# C_20.net
KiCad netlist of a schematic drawn in Altium Designer
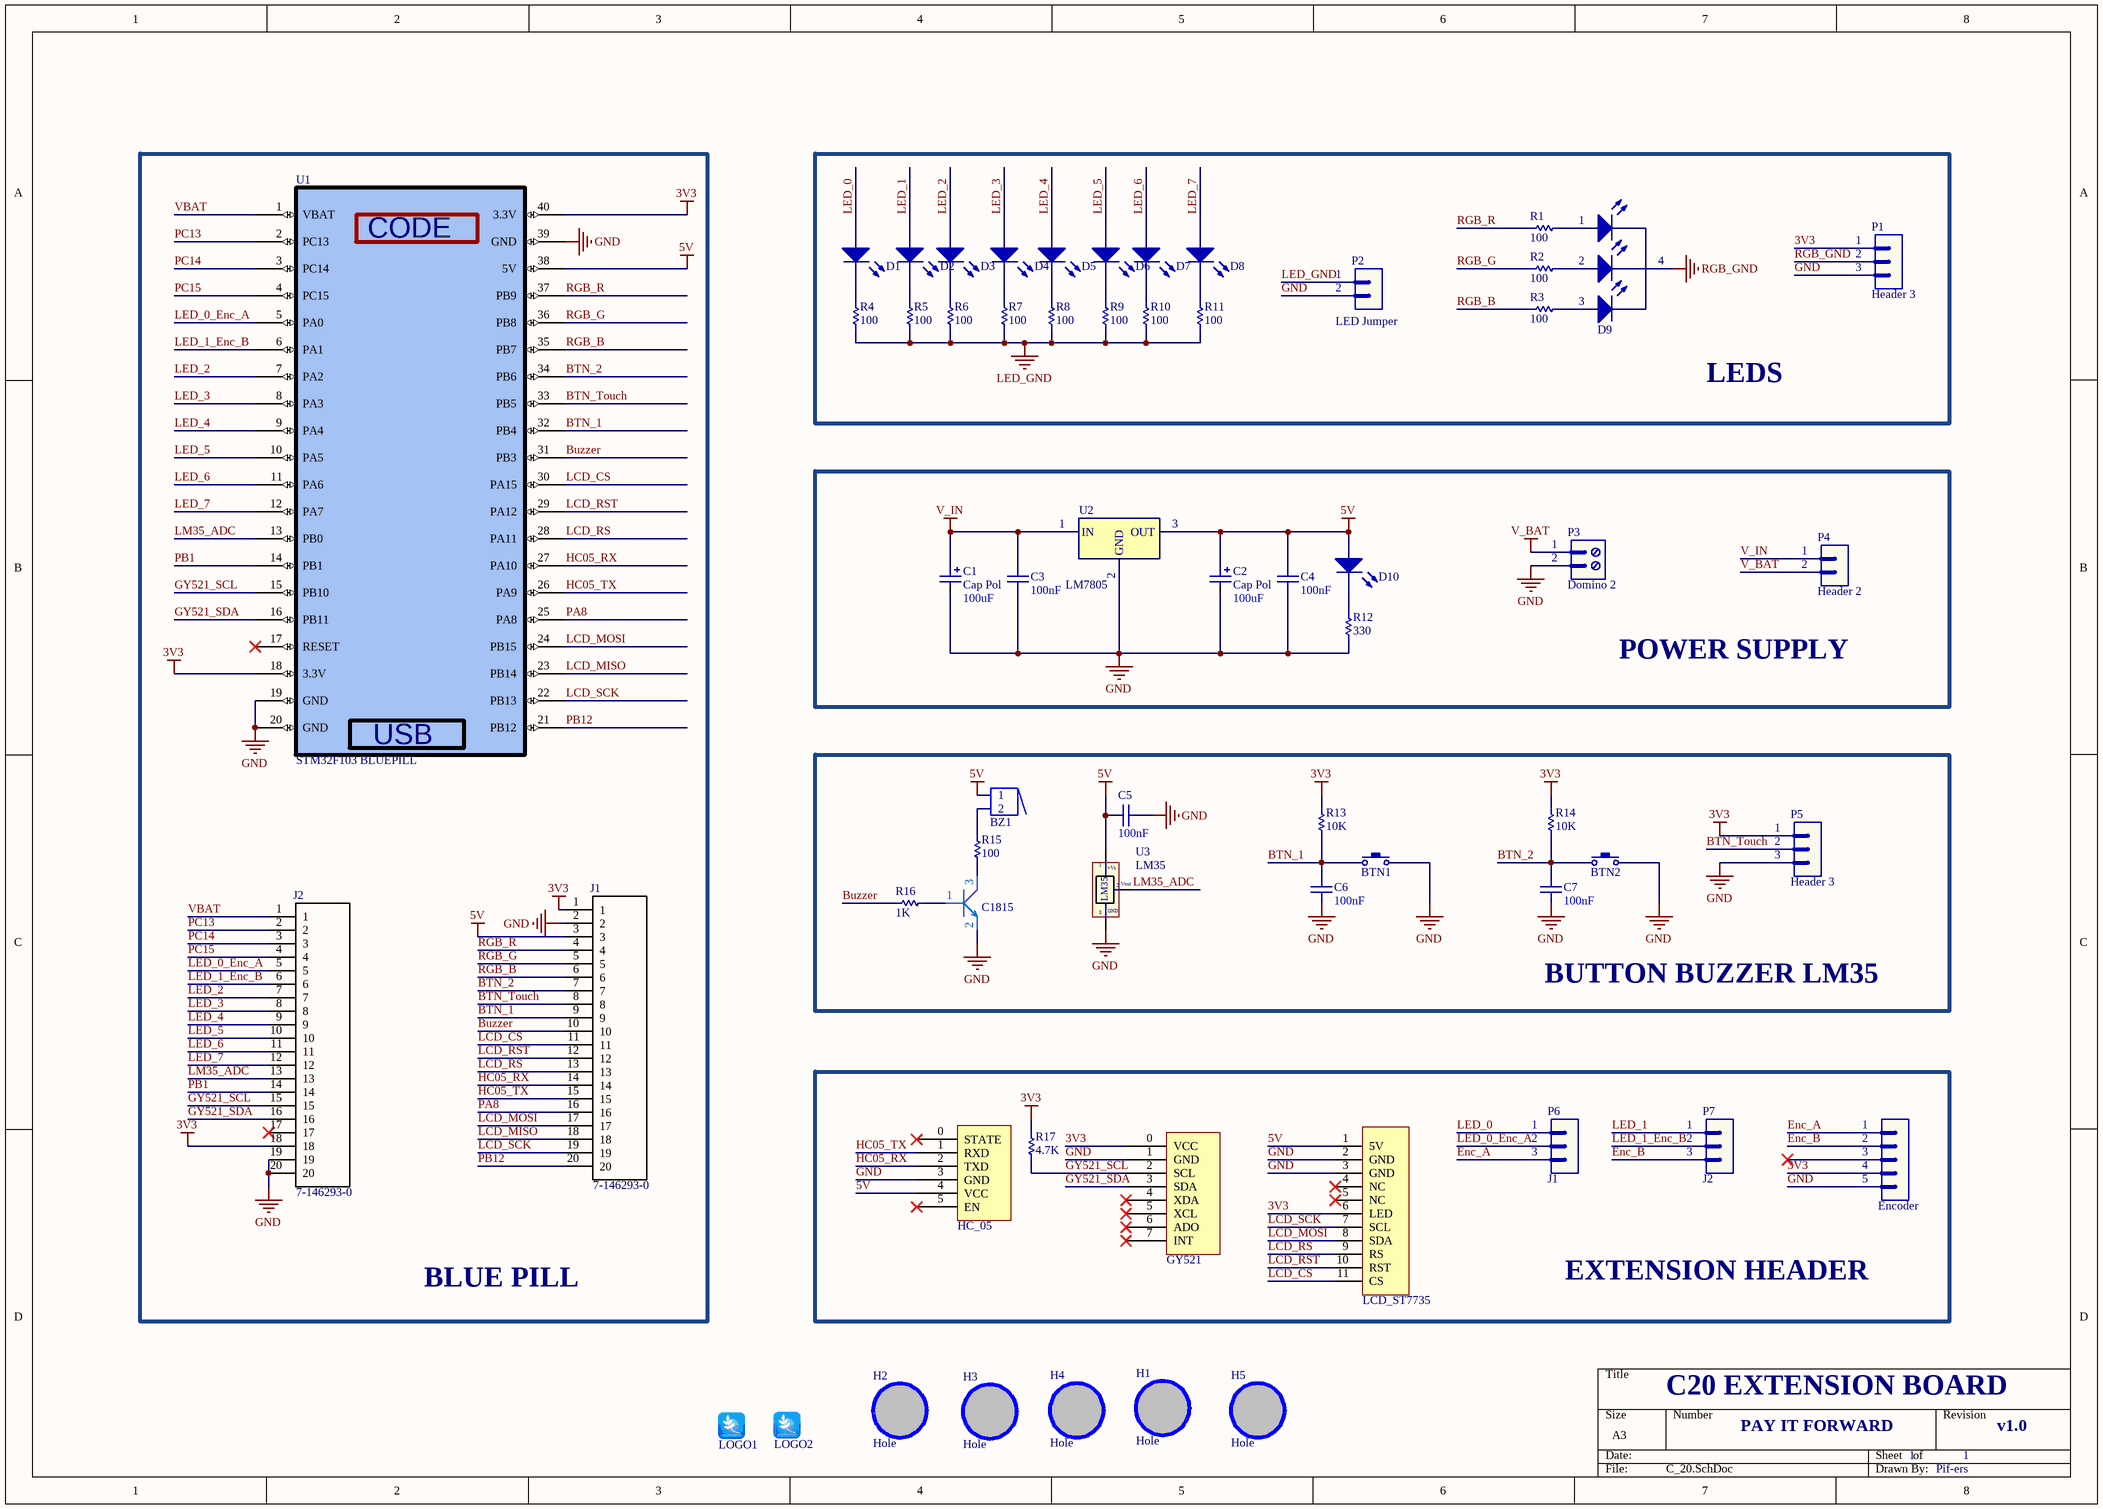
[diagram p0: C_20.SchDoc]

(export (version "E")
  (design (tool "Eeschema 10.0.6"))
  (components
    (comp (ref "BTN1")
      (value "Button")
      (footprint "Button")
      (libsource (lib "PIF_C16_2_lib") (part "Button"))
    )
    (comp (ref "BTN2")
      (value "Button")
      (footprint "Button")
      (libsource (lib "PIF_C16_2_lib") (part "Button"))
    )
    (comp (ref "BZ1") (value "Buzzer") (footprint "BUZZER") (libsource (lib "PIF_C16_2_lib") (part "Buzzer")))
    (comp (ref "C1")
      (value "Cap Pol")
      (footprint "CP1/2")
      (description "Polarized Capacitor (Radial)")
      (fields (field (name "ALTIUM_VALUE") "100uF"))
      (libsource (lib "PIF_C16_2_lib") (part "Cap Pol"))
    )
    (comp (ref "C2")
      (value "Cap Pol")
      (footprint "CP1/2")
      (description "Polarized Capacitor (Radial)")
      (fields (field (name "ALTIUM_VALUE") "100uF"))
      (libsource (lib "PIF_C16_2_lib") (part "Cap Pol"))
    )
    (comp (ref "C3")
      (value "100nF")
      (footprint "CAP-SM-0805")
      (description "Capacitor")
      (fields (field (name "Comment") "Cap Non-Pol SMD"))
      (libsource (lib "PIF_C16_2_lib") (part "Cap Non-Pol SMD"))
    )
    (comp (ref "C4")
      (value "100nF")
      (footprint "CAP-SM-0805")
      (description "Capacitor")
      (fields (field (name "Comment") "Cap Non-Pol SMD"))
      (libsource (lib "PIF_C16_2_lib") (part "Cap Non-Pol SMD"))
    )
    (comp (ref "C5")
      (value "100nF")
      (footprint "CAP-SM-0805")
      (description "Capacitor")
      (fields (field (name "Comment") "Cap Non-Pol SMD"))
      (libsource (lib "PIF_C16_2_lib") (part "Cap Non-Pol SMD"))
    )
    (comp (ref "C6")
      (value "100nF")
      (footprint "CAP-SM-0805")
      (description "Capacitor")
      (fields (field (name "Comment") "Cap Non-Pol SMD"))
      (libsource (lib "PIF_C16_2_lib") (part "Cap Non-Pol SMD"))
    )
    (comp (ref "C7")
      (value "100nF")
      (footprint "CAP-SM-0805")
      (description "Capacitor")
      (fields (field (name "Comment") "Cap Non-Pol SMD"))
      (libsource (lib "PIF_C16_2_lib") (part "Cap Non-Pol SMD"))
    )
    (comp (ref "C8") (value "C1815") (footprint "C1815_SMD") (libsource (lib "C_20_addition") (part "C1815")))
    (comp (ref "D1") (value "LED") (footprint "LED-3mm") (libsource (lib "PIF_C16_2_lib") (part "LED")))
    (comp (ref "D2") (value "LED") (footprint "LED-3mm") (libsource (lib "PIF_C16_2_lib") (part "LED")))
    (comp (ref "D3") (value "LED") (footprint "LED-3mm") (libsource (lib "PIF_C16_2_lib") (part "LED")))
    (comp (ref "D4") (value "LED") (footprint "LED-3mm") (libsource (lib "PIF_C16_2_lib") (part "LED")))
    (comp (ref "D5") (value "LED") (footprint "LED-3mm") (libsource (lib "PIF_C16_2_lib") (part "LED")))
    (comp (ref "D6") (value "LED") (footprint "LED-3mm") (libsource (lib "PIF_C16_2_lib") (part "LED")))
    (comp (ref "D7") (value "LED") (footprint "LED-3mm") (libsource (lib "PIF_C16_2_lib") (part "LED")))
    (comp (ref "D8") (value "LED") (footprint "LED-3mm") (libsource (lib "PIF_C16_2_lib") (part "LED")))
    (comp (ref "D9")
      (value "LED RGB")
      (footprint "LED RGB")
      (libsource (lib "PIF_C16_2_lib") (part "LED RGB"))
    )
    (comp (ref "D10") (value "LED") (footprint "LED-3mm") (libsource (lib "PIF_C16_2_lib") (part "LED")))
    (comp (ref "Encoder")
      (value "Encoder")
      (footprint "JP5")
      (description "Header, 5-Pin")
      (fields (field (name "PUBLISHER") "Altium Limited"))
      (libsource (lib "PIF_C16_2_lib") (part "Header 5"))
    )
    (comp (ref "H1")
      (value "Hole")
      (footprint "LO KHOAN 3MM")
      (description "Hole 3mm")
      (libsource (lib "PIF_C16_2_lib") (part "Hole"))
    )
    (comp (ref "H2")
      (value "Hole")
      (footprint "LO KHOAN 3MM")
      (description "Hole 3mm")
      (libsource (lib "PIF_C16_2_lib") (part "Hole"))
    )
    (comp (ref "H3")
      (value "Hole")
      (footprint "LO KHOAN 3MM")
      (description "Hole 3mm")
      (libsource (lib "PIF_C16_2_lib") (part "Hole"))
    )
    (comp (ref "H4")
      (value "Hole")
      (footprint "LO KHOAN 3MM")
      (description "Hole 3mm")
      (libsource (lib "PIF_C16_2_lib") (part "Hole"))
    )
    (comp (ref "H5")
      (value "Hole")
      (footprint "LO KHOAN 3MM")
      (description "Hole 3mm")
      (libsource (lib "PIF_C16_2_lib") (part "Hole"))
    )
    (comp (ref "HC_05") (value "HC_05") (footprint "HC_05") (libsource (lib "C_20_addition") (part "HC_05")))
    (comp (ref "J1")
      (value "7-146293-0")
      (footprint "*TE_7-146293-0")
      (libsource (lib "7-146293-0") (part "7-146293-0"))
    )
    (comp (ref "J2")
      (value "7-146293-0")
      (footprint "*TE_7-146293-0")
      (libsource (lib "7-146293-0") (part "7-146293-0"))
    )
    (comp (ref "LCD_ST7735")
      (value "LCD_ST7735")
      (footprint "LCD_ST7735")
      (libsource (lib "C_20_addition") (part "LCD_ST7735"))
    )
    (comp (ref "LOGO1")
      (value "LOGO PIF")
      (footprint "PIF LOGO TOP OVERLAY")
      (libsource (lib "logo_PIF") (part "LOGO PIF"))
    )
    (comp (ref "LOGO2")
      (value "LOGO PIF")
      (footprint "PIF LOGO BOTTOM LAYER")
      (libsource (lib "logo_PIF") (part "LOGO PIF"))
    )
    (comp (ref "MPU6050")
      (value "GY521")
      (footprint "GY521_MPU6050")
      (libsource (lib "C_20_addition") (part "GY521_MPU6050"))
    )
    (comp (ref "P1")
      (value "Header 3")
      (footprint "JP3")
      (description "Header, 3-Pin")
      (fields (field (name "PUBLISHER") "Altium Limited"))
      (libsource (lib "PIF_C16_2_lib") (part "Header 3"))
    )
    (comp (ref "P2")
      (value "LED Jumper")
      (footprint "JP2")
      (description "Header, 2-Pin")
      (fields (field (name "PUBLISHER") "Altium Limited"))
      (libsource (lib "PIF_C16_2_lib") (part "Header 2"))
    )
    (comp (ref "P3")
      (value "Domino 2")
      (footprint "DOMINO 2- 5mm")
      (description "Domino, 2-Pin")
      (fields (field (name "PUBLISHER") "Altium Limited"))
      (libsource (lib "PIF_C16_2_lib") (part "Domino 2"))
    )
    (comp (ref "P4")
      (value "Header 2")
      (footprint "JP2")
      (description "Header, 2-Pin")
      (fields (field (name "PUBLISHER") "Altium Limited"))
      (libsource (lib "PIF_C16_2_lib") (part "Header 2"))
    )
    (comp (ref "P5")
      (value "Header 3")
      (footprint "JP3")
      (description "Header, 3-Pin")
      (fields (field (name "PUBLISHER") "Altium Limited"))
      (libsource (lib "PIF_C16_2_lib") (part "Header 3"))
    )
    (comp (ref "P6")
      (value "J1")
      (footprint "JP3")
      (description "Header, 3-Pin")
      (fields (field (name "PUBLISHER") "Altium Limited"))
      (libsource (lib "PIF_C16_2_lib") (part "Header 3"))
    )
    (comp (ref "P7")
      (value "J2")
      (footprint "JP3")
      (description "Header, 3-Pin")
      (fields (field (name "PUBLISHER") "Altium Limited"))
      (libsource (lib "PIF_C16_2_lib") (part "Header 3"))
    )
    (comp (ref "R1")
      (value "100")
      (footprint "RES-SM-0805")
      (fields (field (name "Comment") "Resistor 1/4W"))
      (libsource (lib "PIF_C16_2_lib") (part "RES"))
    )
    (comp (ref "R2")
      (value "100")
      (footprint "RES-SM-0805")
      (fields (field (name "Comment") "Resistor 1/4W"))
      (libsource (lib "PIF_C16_2_lib") (part "RES"))
    )
    (comp (ref "R3")
      (value "100")
      (footprint "RES-SM-0805")
      (fields (field (name "Comment") "Resistor 1/4W"))
      (libsource (lib "PIF_C16_2_lib") (part "RES"))
    )
    (comp (ref "R4")
      (value "100")
      (footprint "RES-SM-0805")
      (fields (field (name "Comment") "Resistor 1/4W"))
      (libsource (lib "PIF_C16_2_lib") (part "RES"))
    )
    (comp (ref "R5")
      (value "100")
      (footprint "RES-SM-0805")
      (fields (field (name "Comment") "Resistor 1/4W"))
      (libsource (lib "PIF_C16_2_lib") (part "RES"))
    )
    (comp (ref "R6")
      (value "100")
      (footprint "RES-SM-0805")
      (fields (field (name "Comment") "Resistor 1/4W"))
      (libsource (lib "PIF_C16_2_lib") (part "RES"))
    )
    (comp (ref "R7")
      (value "100")
      (footprint "RES-SM-0805")
      (fields (field (name "Comment") "Resistor 1/4W"))
      (libsource (lib "PIF_C16_2_lib") (part "RES"))
    )
    (comp (ref "R8")
      (value "100")
      (footprint "RES-SM-0805")
      (fields (field (name "Comment") "Resistor 1/4W"))
      (libsource (lib "PIF_C16_2_lib") (part "RES"))
    )
    (comp (ref "R9")
      (value "100")
      (footprint "RES-SM-0805")
      (fields (field (name "Comment") "Resistor 1/4W"))
      (libsource (lib "PIF_C16_2_lib") (part "RES"))
    )
    (comp (ref "R10")
      (value "100")
      (footprint "RES-SM-0805")
      (fields (field (name "Comment") "Resistor 1/4W"))
      (libsource (lib "PIF_C16_2_lib") (part "RES"))
    )
    (comp (ref "R11")
      (value "100")
      (footprint "RES-SM-0805")
      (fields (field (name "Comment") "Resistor 1/4W"))
      (libsource (lib "PIF_C16_2_lib") (part "RES"))
    )
    (comp (ref "R12")
      (value "330")
      (footprint "RES-SM-0805")
      (fields (field (name "Comment") "Resistor 1/4W"))
      (libsource (lib "PIF_C16_2_lib") (part "RES"))
    )
    (comp (ref "R13")
      (value "10K")
      (footprint "RES-SM-0805")
      (fields (field (name "Comment") "Resistor 1/4W"))
      (libsource (lib "PIF_C16_2_lib") (part "RES"))
    )
    (comp (ref "R14")
      (value "10K")
      (footprint "RES-SM-0805")
      (fields (field (name "Comment") "Resistor 1/4W"))
      (libsource (lib "PIF_C16_2_lib") (part "RES"))
    )
    (comp (ref "R15")
      (value "100")
      (footprint "RES-SM-0805")
      (fields (field (name "Comment") "Resistor 1/4W"))
      (libsource (lib "PIF_C16_2_lib") (part "RES"))
    )
    (comp (ref "R16")
      (value "1K")
      (footprint "RES-SM-0805")
      (fields (field (name "Comment") "Resistor 1/4W"))
      (libsource (lib "PIF_C16_2_lib") (part "RES"))
    )
    (comp (ref "R17")
      (value "4.7K")
      (footprint "RES-SM-0805")
      (fields (field (name "Comment") "Resistor 1/4W"))
      (libsource (lib "PIF_C16_2_lib") (part "RES"))
    )
    (comp (ref "U1")
      (value "STM32F103 BLUEPILL")
      (footprint "STM32F103 Bluepill")
      (libsource (lib "BluePillLib") (part "STM32F103 BLUEPILL"))
    )
    (comp (ref "U2")
      (value "LM7805")
      (footprint "QTO-220")
      (description "Positive Voltage Regulator")
      (libsource (lib "PIF_C16_2_lib") (part "LM7805"))
    )
    (comp (ref "U3")
      (value "LM35")
      (footprint "QTO-92")
      (description "Teminal")
      (libsource (lib "syhaunguyen") (part "LM35"))
    )
  )
  (nets
    (net (code "1") (name "/BTN_1") (class "Default")
      (node (ref "BTN1") (pin "1") (pintype "passive"))
      (node (ref "C6") (pin "2") (pinfunction "2_2") (pintype "passive"))
      (node (ref "J1") (pin "9") (pinfunction "9_9") (pintype "passive"))
      (node (ref "R13") (pin "1") (pintype "passive"))
      (node (ref "U1") (pin "32") (pinfunction "PB4_32") (pintype "bidirectional"))
    )
    (net (code "2") (name "/BTN_2") (class "Default")
      (node (ref "BTN2") (pin "1") (pintype "passive"))
      (node (ref "C7") (pin "2") (pinfunction "2_2") (pintype "passive"))
      (node (ref "J1") (pin "7") (pinfunction "7_7") (pintype "passive"))
      (node (ref "R14") (pin "1") (pintype "passive"))
      (node (ref "U1") (pin "34") (pinfunction "PB6_34") (pintype "bidirectional"))
    )
    (net (code "3") (name "/BTN_Touch") (class "Default")
      (node (ref "J1") (pin "8") (pinfunction "8_8") (pintype "passive"))
      (node (ref "P5") (pin "2") (pinfunction "2_2") (pintype "passive"))
      (node (ref "U1") (pin "33") (pinfunction "PB5_33") (pintype "bidirectional"))
    )
    (net (code "4") (name "/Buzzer") (class "Default")
      (node (ref "J1") (pin "10") (pinfunction "10_10") (pintype "passive"))
      (node (ref "R16") (pin "1") (pintype "passive"))
      (node (ref "U1") (pin "31") (pinfunction "PB3_31") (pintype "bidirectional"))
    )
    (net (code "5") (name "/Enc_A") (class "Default")
      (node (ref "Encoder") (pin "1") (pinfunction "1_1") (pintype "passive"))
      (node (ref "P6") (pin "3") (pinfunction "3_3") (pintype "passive"))
    )
    (net (code "6") (name "/Enc_B") (class "Default")
      (node (ref "Encoder") (pin "2") (pinfunction "2_2") (pintype "passive"))
      (node (ref "P7") (pin "3") (pinfunction "3_3") (pintype "passive"))
    )
    (net (code "7") (name "/GY521_SCL") (class "Default")
      (node (ref "J2") (pin "15") (pinfunction "15_15") (pintype "passive"))
      (node (ref "MPU6050") (pin "2") (pinfunction "SCL_2") (pintype "passive"))
      (node (ref "R17") (pin "1") (pintype "passive"))
      (node (ref "U1") (pin "15") (pinfunction "PB10_15") (pintype "bidirectional"))
    )
    (net (code "8") (name "/GY521_SDA") (class "Default")
      (node (ref "J2") (pin "16") (pinfunction "16_16") (pintype "passive"))
      (node (ref "MPU6050") (pin "3") (pinfunction "SDA_3") (pintype "passive"))
      (node (ref "U1") (pin "16") (pinfunction "PB11_16") (pintype "bidirectional"))
    )
    (net (code "9") (name "/HC05_RX") (class "Default")
      (node (ref "HC_05") (pin "2") (pinfunction "TXD_2") (pintype "passive"))
      (node (ref "J1") (pin "14") (pinfunction "14_14") (pintype "passive"))
      (node (ref "U1") (pin "27") (pinfunction "PA10_27") (pintype "bidirectional"))
    )
    (net (code "10") (name "/HC05_TX") (class "Default")
      (node (ref "HC_05") (pin "1") (pinfunction "RXD_1") (pintype "passive"))
      (node (ref "J1") (pin "15") (pinfunction "15_15") (pintype "passive"))
      (node (ref "U1") (pin "26") (pinfunction "PA9_26") (pintype "bidirectional"))
    )
    (net (code "11") (name "/LCD_CS") (class "Default")
      (node (ref "J1") (pin "11") (pinfunction "11_11") (pintype "passive"))
      (node (ref "LCD_ST7735") (pin "11") (pinfunction "CS_11") (pintype "passive"))
      (node (ref "U1") (pin "30") (pinfunction "PA15_30") (pintype "bidirectional"))
    )
    (net (code "12") (name "/LCD_MISO") (class "Default")
      (node (ref "J1") (pin "18") (pinfunction "18_18") (pintype "passive"))
      (node (ref "U1") (pin "23") (pinfunction "PB14_23") (pintype "bidirectional"))
    )
    (net (code "13") (name "/LCD_MOSI") (class "Default")
      (node (ref "J1") (pin "17") (pinfunction "17_17") (pintype "passive"))
      (node (ref "LCD_ST7735") (pin "8") (pinfunction "SDA_8") (pintype "passive"))
      (node (ref "U1") (pin "24") (pinfunction "PB15_24") (pintype "bidirectional"))
    )
    (net (code "14") (name "/LCD_RS") (class "Default")
      (node (ref "J1") (pin "13") (pinfunction "13_13") (pintype "passive"))
      (node (ref "LCD_ST7735") (pin "9") (pinfunction "RS_9") (pintype "passive"))
      (node (ref "U1") (pin "28") (pinfunction "PA11_28") (pintype "bidirectional"))
    )
    (net (code "15") (name "/LCD_RST") (class "Default")
      (node (ref "J1") (pin "12") (pinfunction "12_12") (pintype "passive"))
      (node (ref "LCD_ST7735") (pin "10") (pinfunction "RST_10") (pintype "passive"))
      (node (ref "U1") (pin "29") (pinfunction "PA12_29") (pintype "bidirectional"))
    )
    (net (code "16") (name "/LCD_SCK") (class "Default")
      (node (ref "J1") (pin "19") (pinfunction "19_19") (pintype "passive"))
      (node (ref "LCD_ST7735") (pin "7") (pinfunction "SCL_7") (pintype "passive"))
      (node (ref "U1") (pin "22") (pinfunction "PB13_22") (pintype "bidirectional"))
    )
    (net (code "17") (name "/LED_0") (class "Default")
      (node (ref "D1") (pin "1") (pinfunction "A_1") (pintype "passive"))
      (node (ref "P6") (pin "1") (pinfunction "1_1") (pintype "passive"))
    )
    (net (code "18") (name "/LED_0_Enc_A") (class "Default")
      (node (ref "J2") (pin "5") (pinfunction "5_5") (pintype "passive"))
      (node (ref "P6") (pin "2") (pinfunction "2_2") (pintype "passive"))
      (node (ref "U1") (pin "5") (pinfunction "PA0_5") (pintype "bidirectional"))
    )
    (net (code "19") (name "/LED_1") (class "Default")
      (node (ref "D2") (pin "1") (pinfunction "A_1") (pintype "passive"))
      (node (ref "P7") (pin "1") (pinfunction "1_1") (pintype "passive"))
    )
    (net (code "20") (name "/LED_1_Enc_B") (class "Default")
      (node (ref "J2") (pin "6") (pinfunction "6_6") (pintype "passive"))
      (node (ref "P7") (pin "2") (pinfunction "2_2") (pintype "passive"))
      (node (ref "U1") (pin "6") (pinfunction "PA1_6") (pintype "bidirectional"))
    )
    (net (code "21") (name "/LED_2") (class "Default")
      (node (ref "D3") (pin "1") (pinfunction "A_1") (pintype "passive"))
      (node (ref "J2") (pin "7") (pinfunction "7_7") (pintype "passive"))
      (node (ref "U1") (pin "7") (pinfunction "PA2_7") (pintype "bidirectional"))
    )
    (net (code "22") (name "/LED_3") (class "Default")
      (node (ref "D4") (pin "1") (pinfunction "A_1") (pintype "passive"))
      (node (ref "J2") (pin "8") (pinfunction "8_8") (pintype "passive"))
      (node (ref "U1") (pin "8") (pinfunction "PA3_8") (pintype "bidirectional"))
    )
    (net (code "23") (name "/LED_4") (class "Default")
      (node (ref "D5") (pin "1") (pinfunction "A_1") (pintype "passive"))
      (node (ref "J2") (pin "9") (pinfunction "9_9") (pintype "passive"))
      (node (ref "U1") (pin "9") (pinfunction "PA4_9") (pintype "bidirectional"))
    )
    (net (code "24") (name "/LED_5") (class "Default")
      (node (ref "D6") (pin "1") (pinfunction "A_1") (pintype "passive"))
      (node (ref "J2") (pin "10") (pinfunction "10_10") (pintype "passive"))
      (node (ref "U1") (pin "10") (pinfunction "PA5_10") (pintype "bidirectional"))
    )
    (net (code "25") (name "/LED_6") (class "Default")
      (node (ref "D7") (pin "1") (pinfunction "A_1") (pintype "passive"))
      (node (ref "J2") (pin "11") (pinfunction "11_11") (pintype "passive"))
      (node (ref "U1") (pin "11") (pinfunction "PA6_11") (pintype "bidirectional"))
    )
    (net (code "26") (name "/LED_7") (class "Default")
      (node (ref "D8") (pin "1") (pinfunction "A_1") (pintype "passive"))
      (node (ref "J2") (pin "12") (pinfunction "12_12") (pintype "passive"))
      (node (ref "U1") (pin "12") (pinfunction "PA7_12") (pintype "bidirectional"))
    )
    (net (code "27") (name "/LM35_ADC") (class "Default")
      (node (ref "J2") (pin "13") (pinfunction "13_13") (pintype "passive"))
      (node (ref "U1") (pin "13") (pinfunction "PB0_13") (pintype "bidirectional"))
      (node (ref "U3") (pin "2") (pinfunction "Vout_2") (pintype "passive"))
    )
    (net (code "28") (name "/PA8") (class "Default")
      (node (ref "J1") (pin "16") (pinfunction "16_16") (pintype "passive"))
      (node (ref "U1") (pin "25") (pinfunction "PA8_25") (pintype "bidirectional"))
    )
    (net (code "29") (name "/PB1") (class "Default")
      (node (ref "J2") (pin "14") (pinfunction "14_14") (pintype "passive"))
      (node (ref "U1") (pin "14") (pinfunction "PB1_14") (pintype "bidirectional"))
    )
    (net (code "30") (name "/PB12") (class "Default")
      (node (ref "J1") (pin "20") (pinfunction "20_20") (pintype "passive"))
      (node (ref "U1") (pin "21") (pinfunction "PB12_21") (pintype "bidirectional"))
    )
    (net (code "31") (name "/PC13") (class "Default")
      (node (ref "J2") (pin "2") (pinfunction "2_2") (pintype "passive"))
      (node (ref "U1") (pin "2") (pinfunction "PC13_2") (pintype "bidirectional"))
    )
    (net (code "32") (name "/PC14") (class "Default")
      (node (ref "J2") (pin "3") (pinfunction "3_3") (pintype "passive"))
      (node (ref "U1") (pin "3") (pinfunction "PC14_3") (pintype "bidirectional"))
    )
    (net (code "33") (name "/PC15") (class "Default")
      (node (ref "J2") (pin "4") (pinfunction "4_4") (pintype "passive"))
      (node (ref "U1") (pin "4") (pinfunction "PC15_4") (pintype "bidirectional"))
    )
    (net (code "34") (name "/RGB_B") (class "Default")
      (node (ref "J1") (pin "6") (pinfunction "6_6") (pintype "passive"))
      (node (ref "R3") (pin "1") (pintype "passive"))
      (node (ref "U1") (pin "35") (pinfunction "PB7_35") (pintype "bidirectional"))
    )
    (net (code "35") (name "/RGB_G") (class "Default")
      (node (ref "J1") (pin "5") (pinfunction "5_5") (pintype "passive"))
      (node (ref "R2") (pin "1") (pintype "passive"))
      (node (ref "U1") (pin "36") (pinfunction "PB8_36") (pintype "bidirectional"))
    )
    (net (code "36") (name "/RGB_R") (class "Default")
      (node (ref "J1") (pin "4") (pinfunction "4_4") (pintype "passive"))
      (node (ref "R1") (pin "1") (pintype "passive"))
      (node (ref "U1") (pin "37") (pinfunction "PB9_37") (pintype "bidirectional"))
    )
    (net (code "37") (name "/VBAT") (class "Default")
      (node (ref "J2") (pin "1") (pinfunction "1_1") (pintype "passive"))
      (node (ref "U1") (pin "1") (pinfunction "VBAT_1") (pintype "bidirectional"))
    )
    (net (code "38") (name "3V3") (class "Default")
      (node (ref "Encoder") (pin "4") (pinfunction "4_4") (pintype "passive"))
      (node (ref "J1") (pin "1") (pinfunction "1_1") (pintype "passive"))
      (node (ref "J2") (pin "18") (pinfunction "18_18") (pintype "passive"))
      (node (ref "LCD_ST7735") (pin "6") (pinfunction "LED_6") (pintype "passive"))
      (node (ref "MPU6050") (pin "0") (pinfunction "VCC_0") (pintype "passive"))
      (node (ref "P1") (pin "1") (pinfunction "1_1") (pintype "passive"))
      (node (ref "P5") (pin "1") (pinfunction "1_1") (pintype "passive"))
      (node (ref "R13") (pin "2") (pintype "passive"))
      (node (ref "R14") (pin "2") (pintype "passive"))
      (node (ref "R17") (pin "2") (pintype "passive"))
      (node (ref "U1") (pin "18") (pinfunction "3.3V_18") (pintype "bidirectional"))
      (node (ref "U1") (pin "40") (pinfunction "3.3V_40") (pintype "bidirectional"))
    )
    (net (code "39") (name "5V") (class "Default")
      (node (ref "BZ1") (pin "1") (pinfunction "1_1") (pintype "passive"))
      (node (ref "C2") (pin "1") (pinfunction "1_1") (pintype "passive"))
      (node (ref "C4") (pin "2") (pinfunction "2_2") (pintype "passive"))
      (node (ref "C5") (pin "1") (pinfunction "1_1") (pintype "passive"))
      (node (ref "D10") (pin "1") (pinfunction "A_1") (pintype "passive"))
      (node (ref "HC_05") (pin "4") (pinfunction "VCC_4") (pintype "passive"))
      (node (ref "J1") (pin "3") (pinfunction "3_3") (pintype "passive"))
      (node (ref "LCD_ST7735") (pin "1") (pinfunction "5V_1") (pintype "passive"))
      (node (ref "U1") (pin "38") (pinfunction "5V_38") (pintype "bidirectional"))
      (node (ref "U2") (pin "3") (pinfunction "OUT_3") (pintype "power_in"))
      (node (ref "U3") (pin "1") (pinfunction "+Vs_1") (pintype "passive"))
    )
    (net (code "40") (name "GND") (class "Default")
      (node (ref "BTN1") (pin "2") (pintype "passive"))
      (node (ref "BTN2") (pin "2") (pintype "passive"))
      (node (ref "C1") (pin "2") (pinfunction "2_2") (pintype "passive"))
      (node (ref "C2") (pin "2") (pinfunction "2_2") (pintype "passive"))
      (node (ref "C3") (pin "1") (pinfunction "1_1") (pintype "passive"))
      (node (ref "C4") (pin "1") (pinfunction "1_1") (pintype "passive"))
      (node (ref "C5") (pin "2") (pinfunction "2_2") (pintype "passive"))
      (node (ref "C6") (pin "1") (pinfunction "1_1") (pintype "passive"))
      (node (ref "C7") (pin "1") (pinfunction "1_1") (pintype "passive"))
      (node (ref "C8") (pin "2") (pinfunction "C_2") (pintype "passive"))
      (node (ref "Encoder") (pin "5") (pinfunction "5_5") (pintype "passive"))
      (node (ref "HC_05") (pin "3") (pinfunction "GND_3") (pintype "passive"))
      (node (ref "J1") (pin "2") (pinfunction "2_2") (pintype "passive"))
      (node (ref "J2") (pin "19") (pinfunction "19_19") (pintype "passive"))
      (node (ref "J2") (pin "20") (pinfunction "20_20") (pintype "passive"))
      (node (ref "LCD_ST7735") (pin "2") (pinfunction "GND_2") (pintype "passive"))
      (node (ref "LCD_ST7735") (pin "3") (pinfunction "GND_3") (pintype "passive"))
      (node (ref "MPU6050") (pin "1") (pinfunction "GND_1") (pintype "passive"))
      (node (ref "P1") (pin "3") (pinfunction "3_3") (pintype "passive"))
      (node (ref "P2") (pin "2") (pinfunction "2_2") (pintype "passive"))
      (node (ref "P3") (pin "2") (pinfunction "2_2") (pintype "passive"))
      (node (ref "P5") (pin "3") (pinfunction "3_3") (pintype "passive"))
      (node (ref "R12") (pin "1") (pintype "passive"))
      (node (ref "U1") (pin "19") (pinfunction "GND_19") (pintype "bidirectional"))
      (node (ref "U1") (pin "20") (pinfunction "GND_20") (pintype "bidirectional"))
      (node (ref "U1") (pin "39") (pinfunction "GND_39") (pintype "bidirectional"))
      (node (ref "U2") (pin "2") (pinfunction "GND_2") (pintype "power_in"))
      (node (ref "U3") (pin "3") (pinfunction "-_3") (pintype "passive"))
    )
    (net (code "41") (name "LED_GND") (class "Default")
      (node (ref "P2") (pin "1") (pinfunction "1_1") (pintype "passive"))
      (node (ref "R10") (pin "1") (pintype "passive"))
      (node (ref "R11") (pin "1") (pintype "passive"))
      (node (ref "R4") (pin "1") (pintype "passive"))
      (node (ref "R5") (pin "1") (pintype "passive"))
      (node (ref "R6") (pin "1") (pintype "passive"))
      (node (ref "R7") (pin "1") (pintype "passive"))
      (node (ref "R8") (pin "1") (pintype "passive"))
      (node (ref "R9") (pin "1") (pintype "passive"))
    )
    (net (code "42") (name "Net-(BZ1-Pad2)") (class "Default")
      (node (ref "BZ1") (pin "2") (pinfunction "2_2") (pintype "passive"))
      (node (ref "R15") (pin "2") (pintype "passive"))
    )
    (net (code "43") (name "Net-(C8-B)") (class "Default")
      (node (ref "C8") (pin "1") (pinfunction "B_1") (pintype "passive"))
      (node (ref "R16") (pin "2") (pintype "passive"))
    )
    (net (code "44") (name "Net-(C8-C-Pad3)") (class "Default")
      (node (ref "C8") (pin "3") (pinfunction "C_3") (pintype "passive"))
      (node (ref "R15") (pin "1") (pintype "passive"))
    )
    (net (code "45") (name "Net-(D1-K)") (class "Default")
      (node (ref "D1") (pin "2") (pinfunction "K_2") (pintype "passive"))
      (node (ref "R4") (pin "2") (pintype "passive"))
    )
    (net (code "46") (name "Net-(D2-K)") (class "Default")
      (node (ref "D2") (pin "2") (pinfunction "K_2") (pintype "passive"))
      (node (ref "R5") (pin "2") (pintype "passive"))
    )
    (net (code "47") (name "Net-(D3-K)") (class "Default")
      (node (ref "D3") (pin "2") (pinfunction "K_2") (pintype "passive"))
      (node (ref "R6") (pin "2") (pintype "passive"))
    )
    (net (code "48") (name "Net-(D4-K)") (class "Default")
      (node (ref "D4") (pin "2") (pinfunction "K_2") (pintype "passive"))
      (node (ref "R7") (pin "2") (pintype "passive"))
    )
    (net (code "49") (name "Net-(D5-K)") (class "Default")
      (node (ref "D5") (pin "2") (pinfunction "K_2") (pintype "passive"))
      (node (ref "R8") (pin "2") (pintype "passive"))
    )
    (net (code "50") (name "Net-(D6-K)") (class "Default")
      (node (ref "D6") (pin "2") (pinfunction "K_2") (pintype "passive"))
      (node (ref "R9") (pin "2") (pintype "passive"))
    )
    (net (code "51") (name "Net-(D7-K)") (class "Default")
      (node (ref "D7") (pin "2") (pinfunction "K_2") (pintype "passive"))
      (node (ref "R10") (pin "2") (pintype "passive"))
    )
    (net (code "52") (name "Net-(D8-K)") (class "Default")
      (node (ref "D8") (pin "2") (pinfunction "K_2") (pintype "passive"))
      (node (ref "R11") (pin "2") (pintype "passive"))
    )
    (net (code "53") (name "Net-(D9-Anod-Pad1)") (class "Default")
      (node (ref "D9") (pin "1") (pinfunction "Anod_1") (pintype "passive"))
      (node (ref "R1") (pin "2") (pintype "passive"))
    )
    (net (code "54") (name "Net-(D9-Anod-Pad2)") (class "Default")
      (node (ref "D9") (pin "2") (pinfunction "Anod_2") (pintype "passive"))
      (node (ref "R2") (pin "2") (pintype "passive"))
    )
    (net (code "55") (name "Net-(D9-Anod-Pad3)") (class "Default")
      (node (ref "D9") (pin "3") (pinfunction "Anod_3") (pintype "passive"))
      (node (ref "R3") (pin "2") (pintype "passive"))
    )
    (net (code "56") (name "Net-(D10-K)") (class "Default")
      (node (ref "D10") (pin "2") (pinfunction "K_2") (pintype "passive"))
      (node (ref "R12") (pin "2") (pintype "passive"))
    )
    (net (code "57") (name "RGB_GND") (class "Default")
      (node (ref "D9") (pin "4") (pinfunction "Anod_4") (pintype "passive"))
      (node (ref "P1") (pin "2") (pinfunction "2_2") (pintype "passive"))
    )
    (net (code "58") (name "V_BAT") (class "Default")
      (node (ref "P3") (pin "1") (pinfunction "1_1") (pintype "passive"))
      (node (ref "P4") (pin "2") (pinfunction "2_2") (pintype "passive"))
    )
    (net (code "59") (name "V_IN") (class "Default")
      (node (ref "C1") (pin "1") (pinfunction "1_1") (pintype "passive"))
      (node (ref "C3") (pin "2") (pinfunction "2_2") (pintype "passive"))
      (node (ref "P4") (pin "1") (pinfunction "1_1") (pintype "passive"))
      (node (ref "U2") (pin "1") (pinfunction "IN_1") (pintype "power_in"))
    )
    (net (code "60") (name "unconnected-(Encoder-Pad3)") (class "Default")
      (node (ref "Encoder") (pin "3") (pinfunction "3_3") (pintype "passive+no_connect"))
    )
    (net (code "61") (name "unconnected-(H1-Pad1)") (class "Default")
      (node (ref "H1") (pin "1") (pinfunction "1_1") (pintype "passive"))
    )
    (net (code "62") (name "unconnected-(H2-Pad1)") (class "Default")
      (node (ref "H2") (pin "1") (pinfunction "1_1") (pintype "passive"))
    )
    (net (code "63") (name "unconnected-(H3-Pad1)") (class "Default")
      (node (ref "H3") (pin "1") (pinfunction "1_1") (pintype "passive"))
    )
    (net (code "64") (name "unconnected-(H4-Pad1)") (class "Default")
      (node (ref "H4") (pin "1") (pinfunction "1_1") (pintype "passive"))
    )
    (net (code "65") (name "unconnected-(H5-Pad1)") (class "Default")
      (node (ref "H5") (pin "1") (pinfunction "1_1") (pintype "passive"))
    )
    (net (code "66") (name "unconnected-(HC_05-EN-Pad5)") (class "Default")
      (node (ref "HC_05") (pin "5") (pinfunction "EN_5") (pintype "passive+no_connect"))
    )
    (net (code "67") (name "unconnected-(HC_05-STATE-Pad0)") (class "Default")
      (node (ref "HC_05") (pin "0") (pinfunction "STATE_0") (pintype "passive+no_connect"))
    )
    (net (code "68") (name "unconnected-(J2-Pad17)") (class "Default")
      (node (ref "J2") (pin "17") (pinfunction "17_17") (pintype "passive+no_connect"))
    )
    (net (code "69") (name "unconnected-(LCD_ST7735-NC-Pad4)") (class "Default")
      (node (ref "LCD_ST7735") (pin "4") (pinfunction "NC_4") (pintype "passive+no_connect"))
    )
    (net (code "70") (name "unconnected-(LCD_ST7735-NC-Pad5)") (class "Default")
      (node (ref "LCD_ST7735") (pin "5") (pinfunction "NC_5") (pintype "passive+no_connect"))
    )
    (net (code "71") (name "unconnected-(MPU6050-ADO-Pad6)") (class "Default")
      (node (ref "MPU6050") (pin "6") (pinfunction "ADO_6") (pintype "passive+no_connect"))
    )
    (net (code "72") (name "unconnected-(MPU6050-INT-Pad7)") (class "Default")
      (node (ref "MPU6050") (pin "7") (pinfunction "INT_7") (pintype "passive+no_connect"))
    )
    (net (code "73") (name "unconnected-(MPU6050-XCL-Pad5)") (class "Default")
      (node (ref "MPU6050") (pin "5") (pinfunction "XCL_5") (pintype "passive+no_connect"))
    )
    (net (code "74") (name "unconnected-(MPU6050-XDA-Pad4)") (class "Default")
      (node (ref "MPU6050") (pin "4") (pinfunction "XDA_4") (pintype "passive+no_connect"))
    )
    (net (code "75") (name "unconnected-(U1-RESET-Pad17)") (class "Default")
      (node (ref "U1") (pin "17") (pinfunction "RESET_17") (pintype "bidirectional+no_connect"))
    )
  )
)
